# KC_Input_VAS_Schematic.net
KiCad netlist of a schematic drawn in Altium Designer
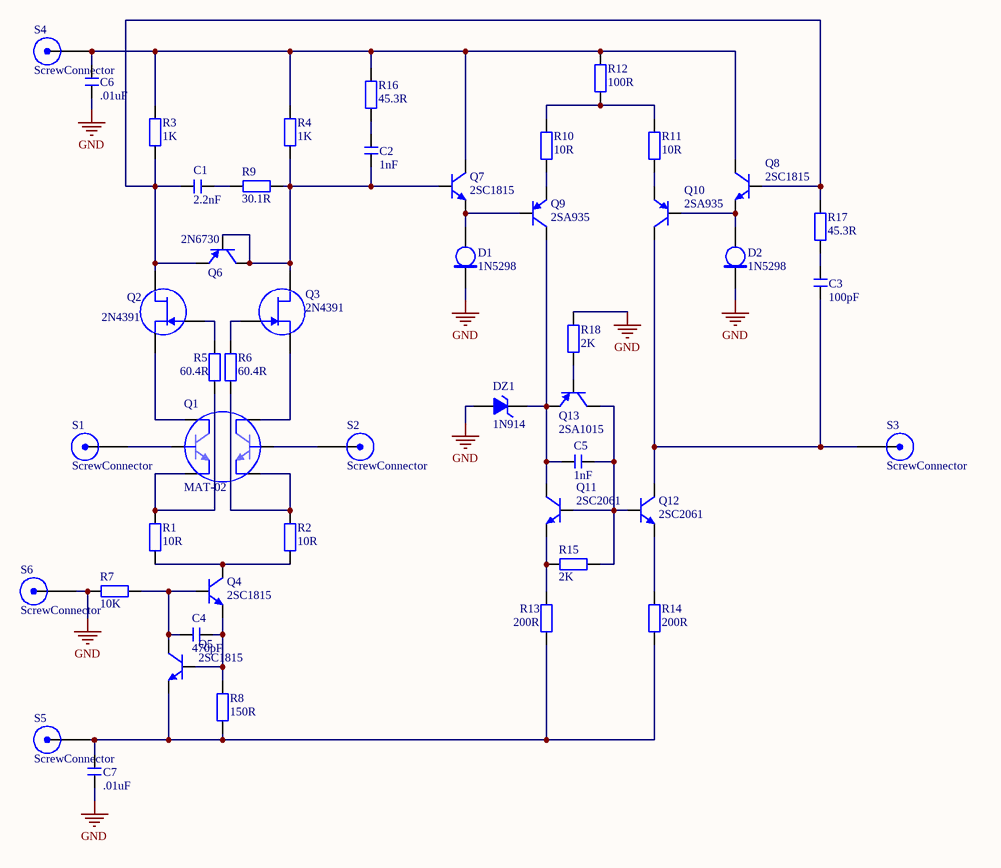
[diagram p0: KC_Input_VAS_Schematic.SchDoc]

(export (version "E")
  (design (tool "Eeschema 10.0.6"))
  (components
    (comp (ref "C1")
      (value "2.2nF")
      (footprint "CBB 6.3*6.3*5")
      (description "CBB电容")
      (fields (field (name "版权归属") "源创客"))
      (libsource (lib "电阻-电容-电感") (part "C-CBB"))
    )
    (comp (ref "C2")
      (value "1nF")
      (footprint "CBB 6.3*6.3*5")
      (description "CBB电容")
      (fields (field (name "版权归属") "源创客"))
      (libsource (lib "电阻-电容-电感") (part "C-CBB"))
    )
    (comp (ref "C3")
      (value "100pF")
      (footprint "CBB 6.3*6.3*5")
      (description "CBB电容")
      (fields (field (name "版权归属") "源创客"))
      (libsource (lib "电阻-电容-电感") (part "C-CBB"))
    )
    (comp (ref "C4")
      (value "470pF")
      (footprint "CBB 6.3*6.3*5")
      (description "CBB电容")
      (fields (field (name "版权归属") "源创客"))
      (libsource (lib "电阻-电容-电感") (part "C-CBB"))
    )
    (comp (ref "C5")
      (value "1nF")
      (footprint "CBB 6.3*6.3*5")
      (description "CBB电容")
      (fields (field (name "版权归属") "源创客"))
      (libsource (lib "电阻-电容-电感") (part "C-CBB"))
    )
    (comp (ref "C6")
      (value ".01uF")
      (footprint "CBB 6.3*6.3*5")
      (description "CBB电容")
      (fields (field (name "版权归属") "源创客"))
      (libsource (lib "电阻-电容-电感") (part "C-CBB"))
    )
    (comp (ref "C7")
      (value ".01uF")
      (footprint "CBB 6.3*6.3*5")
      (description "CBB电容")
      (fields (field (name "版权归属") "源创客"))
      (libsource (lib "电阻-电容-电感") (part "C-CBB"))
    )
    (comp (ref "D1")
      (value "1N5298")
      (footprint "DO-41V")
      (description "Current Regulator Diodes")
      (libsource (lib "二极管-整流桥") (part "1N5xxx"))
    )
    (comp (ref "D2")
      (value "1N5298")
      (footprint "DO-41V")
      (description "Current Regulator Diodes")
      (libsource (lib "二极管-整流桥") (part "1N5xxx"))
    )
    (comp (ref "DZ1")
      (value "1N914")
      (footprint "DO-41")
      (description "3V/0.5W稳压管")
      (fields (field (name "版权归属") "源创客"))
      (libsource (lib "二极管-整流桥") (part "1N4619"))
    )
    (comp (ref "Q1")
      (value "MAT-02")
      (footprint "DIP-8")
      (description "孪生对管-NPN型 40V/20ma")
      (libsource (lib "三极管") (part "MAT-02"))
    )
    (comp (ref "Q2")
      (value "2N4391")
      (footprint "TO-18_SMALLHOLE")
      (description "N沟道JFET开关管 40V/150ma")
      (libsource (lib "场效应管") (part "2N4391"))
    )
    (comp (ref "Q3")
      (value "2N4391")
      (footprint "TO-18_SMALLHOLE")
      (description "N沟道JFET开关管 40V/150ma")
      (libsource (lib "场效应管") (part "2N4391"))
    )
    (comp (ref "Q4")
      (value "2SC1815")
      (footprint "TO92A_SmallHole")
      (description "音频放大-NPN型")
      (libsource (lib "三极管") (part "2SC1815"))
    )
    (comp (ref "Q5")
      (value "2SC1815")
      (footprint "TO92A_SmallHole")
      (description "音频放大-NPN型")
      (libsource (lib "三极管") (part "2SC1815"))
    )
    (comp (ref "Q6")
      (value "2N6730")
      (footprint "TO92A_SmallHole")
      (description "中功率放大-PNP型")
      (libsource (lib "三极管") (part "2N6728/6729/6730"))
    )
    (comp (ref "Q7")
      (value "2SC1815")
      (footprint "TO92A_SmallHole")
      (description "音频放大-NPN型")
      (libsource (lib "三极管") (part "2SC1815"))
    )
    (comp (ref "Q8")
      (value "2SC1815")
      (footprint "TO92A_SmallHole")
      (description "音频放大-NPN型")
      (libsource (lib "三极管") (part "2SC1815"))
    )
    (comp (ref "Q9")
      (value "2SA935")
      (footprint "TO92A_SmallHole")
      (description "音频功放-PNP型 50V/500ma")
      (libsource (lib "三极管") (part "2SA935"))
    )
    (comp (ref "Q10")
      (value "2SA935")
      (footprint "TO92A_SmallHole")
      (description "音频功放-PNP型 50V/500ma")
      (libsource (lib "三极管") (part "2SA935"))
    )
    (comp (ref "Q11")
      (value "2SC2061")
      (footprint "TO92A_SmallHole")
      (description "音频放大-NPN型 50V/500ma")
      (libsource (lib "三极管") (part "2SC2061"))
    )
    (comp (ref "Q12")
      (value "2SC2061")
      (footprint "TO92A_SmallHole")
      (description "音频放大-NPN型 50V/500ma")
      (libsource (lib "三极管") (part "2SC2061"))
    )
    (comp (ref "Q13")
      (value "2SA1015")
      (footprint "TO92A_SmallHole")
      (description "音频放大-PNP型")
      (libsource (lib "三极管") (part "2SA1015"))
    )
    (comp (ref "R1")
      (value "10R")
      (footprint "RS 1/4W")
      (description "直插色环电阻")
      (fields (field (name "版权归属") "源创客"))
      (libsource (lib "电阻-电容-电感") (part "R-CRR"))
    )
    (comp (ref "R2")
      (value "10R")
      (footprint "RS 1/4W")
      (description "直插色环电阻")
      (fields (field (name "版权归属") "源创客"))
      (libsource (lib "电阻-电容-电感") (part "R-CRR"))
    )
    (comp (ref "R3")
      (value "1K")
      (footprint "RS 1/4W")
      (description "直插色环电阻")
      (fields (field (name "版权归属") "源创客"))
      (libsource (lib "电阻-电容-电感") (part "R-CRR"))
    )
    (comp (ref "R4")
      (value "1K")
      (footprint "RS 1/4W")
      (description "直插色环电阻")
      (fields (field (name "版权归属") "源创客"))
      (libsource (lib "电阻-电容-电感") (part "R-CRR"))
    )
    (comp (ref "R5")
      (value "60.4R")
      (footprint "RS 1/4W")
      (description "直插色环电阻")
      (fields (field (name "版权归属") "源创客"))
      (libsource (lib "电阻-电容-电感") (part "R-CRR"))
    )
    (comp (ref "R6")
      (value "60.4R")
      (footprint "RS 1/4W")
      (description "直插色环电阻")
      (fields (field (name "版权归属") "源创客"))
      (libsource (lib "电阻-电容-电感") (part "R-CRR"))
    )
    (comp (ref "R7")
      (value "10K")
      (footprint "RS 1/4W")
      (description "直插色环电阻")
      (fields (field (name "版权归属") "源创客"))
      (libsource (lib "电阻-电容-电感") (part "R-CRR"))
    )
    (comp (ref "R8")
      (value "150R")
      (footprint "RS 1/4W")
      (description "直插色环电阻")
      (fields (field (name "版权归属") "源创客"))
      (libsource (lib "电阻-电容-电感") (part "R-CRR"))
    )
    (comp (ref "R9")
      (value "30.1R")
      (footprint "RS 1/4W")
      (description "直插色环电阻")
      (fields (field (name "版权归属") "源创客"))
      (libsource (lib "电阻-电容-电感") (part "R-CRR"))
    )
    (comp (ref "R10")
      (value "10R")
      (footprint "RS 1/4W")
      (description "直插色环电阻")
      (fields (field (name "版权归属") "源创客"))
      (libsource (lib "电阻-电容-电感") (part "R-CRR"))
    )
    (comp (ref "R11")
      (value "10R")
      (footprint "RS 1/4W")
      (description "直插色环电阻")
      (fields (field (name "版权归属") "源创客"))
      (libsource (lib "电阻-电容-电感") (part "R-CRR"))
    )
    (comp (ref "R12")
      (value "100R")
      (footprint "RS 1/4W")
      (description "直插色环电阻")
      (fields (field (name "版权归属") "源创客"))
      (libsource (lib "电阻-电容-电感") (part "R-CRR"))
    )
    (comp (ref "R13")
      (value "200R")
      (footprint "RS 1/4W")
      (description "直插色环电阻")
      (fields (field (name "版权归属") "源创客"))
      (libsource (lib "电阻-电容-电感") (part "R-CRR"))
    )
    (comp (ref "R14")
      (value "200R")
      (footprint "RS 1/4W")
      (description "直插色环电阻")
      (fields (field (name "版权归属") "源创客"))
      (libsource (lib "电阻-电容-电感") (part "R-CRR"))
    )
    (comp (ref "R15")
      (value "2K")
      (footprint "RS 1/4W")
      (description "直插色环电阻")
      (fields (field (name "版权归属") "源创客"))
      (libsource (lib "电阻-电容-电感") (part "R-CRR"))
    )
    (comp (ref "R16")
      (value "45.3R")
      (footprint "RS 1/4W")
      (description "直插色环电阻")
      (fields (field (name "版权归属") "源创客"))
      (libsource (lib "电阻-电容-电感") (part "R-CRR"))
    )
    (comp (ref "R17")
      (value "45.3R")
      (footprint "RS 1/4W")
      (description "直插色环电阻")
      (fields (field (name "版权归属") "源创客"))
      (libsource (lib "电阻-电容-电感") (part "R-CRR"))
    )
    (comp (ref "R18")
      (value "2K")
      (footprint "RS 1/4W")
      (description "直插色环电阻")
      (fields (field (name "版权归属") "源创客"))
      (libsource (lib "电阻-电容-电感") (part "R-CRR"))
    )
    (comp (ref "S1")
      (value "ScrewConnector")
      (footprint "Screw-M2-s")
      (description "Screw Connector")
      (libsource (lib "Connectors") (part "ScrewConnector"))
    )
    (comp (ref "S2")
      (value "ScrewConnector")
      (footprint "Screw-M2-s")
      (description "Screw Connector")
      (libsource (lib "Connectors") (part "ScrewConnector"))
    )
    (comp (ref "S3")
      (value "ScrewConnector")
      (footprint "Screw-M2-s")
      (description "Screw Connector")
      (libsource (lib "Connectors") (part "ScrewConnector"))
    )
    (comp (ref "S4")
      (value "ScrewConnector")
      (footprint "Screw-M2-s")
      (description "Screw Connector")
      (libsource (lib "Connectors") (part "ScrewConnector"))
    )
    (comp (ref "S5")
      (value "ScrewConnector")
      (footprint "Screw-M2-s")
      (description "Screw Connector")
      (libsource (lib "Connectors") (part "ScrewConnector"))
    )
    (comp (ref "S6")
      (value "ScrewConnector")
      (footprint "Screw-M2-s")
      (description "Screw Connector")
      (libsource (lib "Connectors") (part "ScrewConnector"))
    )
  )
  (nets
    (net (code "1") (name "GND") (class "Default")
      (node (ref "C6") (pin "2") (pinfunction "2_2") (pintype "passive"))
      (node (ref "C7") (pin "1") (pinfunction "1_1") (pintype "passive"))
      (node (ref "D1") (pin "1") (pinfunction "Cathode_1") (pintype "passive"))
      (node (ref "D2") (pin "1") (pinfunction "Cathode_1") (pintype "passive"))
      (node (ref "DZ1") (pin "1") (pinfunction "A_1") (pintype "passive"))
      (node (ref "R18") (pin "2") (pinfunction "2_2") (pintype "passive"))
      (node (ref "R7") (pin "1") (pinfunction "1_1") (pintype "passive"))
      (node (ref "S6") (pin "1") (pinfunction "X_1") (pintype "passive"))
    )
    (net (code "2") (name "Net-(C1-Pad2)") (class "Default")
      (node (ref "C1") (pin "2") (pinfunction "2_2") (pintype "passive"))
      (node (ref "R9") (pin "1") (pinfunction "1_1") (pintype "passive"))
    )
    (net (code "3") (name "Net-(C2-Pad1)") (class "Default")
      (node (ref "C2") (pin "1") (pinfunction "1_1") (pintype "passive"))
      (node (ref "R16") (pin "1") (pinfunction "1_1") (pintype "passive"))
    )
    (net (code "4") (name "Net-(C3-Pad2)") (class "Default")
      (node (ref "C3") (pin "2") (pinfunction "2_2") (pintype "passive"))
      (node (ref "R17") (pin "1") (pinfunction "1_1") (pintype "passive"))
    )
    (net (code "5") (name "Net-(D1-Anode)") (class "Default")
      (node (ref "D1") (pin "2") (pinfunction "Anode_2") (pintype "passive"))
      (node (ref "Q7") (pin "1") (pinfunction "E_1") (pintype "passive"))
      (node (ref "Q9") (pin "3") (pinfunction "B_3") (pintype "passive"))
    )
    (net (code "6") (name "Net-(D2-Anode)") (class "Default")
      (node (ref "D2") (pin "2") (pinfunction "Anode_2") (pintype "passive"))
      (node (ref "Q10") (pin "3") (pinfunction "B_3") (pintype "passive"))
      (node (ref "Q8") (pin "1") (pinfunction "E_1") (pintype "passive"))
    )
    (net (code "7") (name "Net-(DZ1-K)") (class "Default")
      (node (ref "C5") (pin "1") (pinfunction "1_1") (pintype "passive"))
      (node (ref "DZ1") (pin "2") (pinfunction "K_2") (pintype "passive"))
      (node (ref "Q11") (pin "2") (pinfunction "C_2") (pintype "passive"))
      (node (ref "Q13") (pin "1") (pinfunction "E_1") (pintype "passive"))
      (node (ref "Q9") (pin "2") (pinfunction "C_2") (pintype "passive"))
    )
    (net (code "8") (name "Net-(Q1-E-Pad3)") (class "Default")
      (node (ref "Q1") (pin "3") (pinfunction "E_3") (pintype "passive"))
      (node (ref "R1") (pin "2") (pinfunction "2_2") (pintype "passive"))
      (node (ref "R5") (pin "1") (pinfunction "1_1") (pintype "passive"))
    )
    (net (code "9") (name "Net-(Q1-E-Pad5)") (class "Default")
      (node (ref "Q1") (pin "5") (pinfunction "E_5") (pintype "passive"))
      (node (ref "R2") (pin "2") (pinfunction "2_2") (pintype "passive"))
      (node (ref "R6") (pin "1") (pinfunction "1_1") (pintype "passive"))
    )
    (net (code "10") (name "Net-(Q2-D)") (class "Default")
      (node (ref "C1") (pin "1") (pinfunction "1_1") (pintype "passive"))
      (node (ref "Q2") (pin "3") (pinfunction "D_3") (pintype "passive"))
      (node (ref "Q6") (pin "1") (pinfunction "E_1") (pintype "passive"))
      (node (ref "Q8") (pin "3") (pinfunction "B_3") (pintype "passive"))
      (node (ref "R17") (pin "2") (pinfunction "2_2") (pintype "passive"))
      (node (ref "R3") (pin "1") (pinfunction "1_1") (pintype "passive"))
    )
    (net (code "11") (name "Net-(Q2-G)") (class "Default")
      (node (ref "Q2") (pin "2") (pinfunction "G_2") (pintype "passive"))
      (node (ref "R5") (pin "2") (pinfunction "2_2") (pintype "passive"))
    )
    (net (code "12") (name "Net-(Q2-S)") (class "Default")
      (node (ref "Q1") (pin "1") (pinfunction "C_1") (pintype "passive"))
      (node (ref "Q2") (pin "1") (pinfunction "S_1") (pintype "passive"))
    )
    (net (code "13") (name "Net-(Q3-D)") (class "Default")
      (node (ref "C2") (pin "2") (pinfunction "2_2") (pintype "passive"))
      (node (ref "Q3") (pin "3") (pinfunction "D_3") (pintype "passive"))
      (node (ref "Q6") (pin "2") (pinfunction "C_2") (pintype "passive"))
      (node (ref "Q6") (pin "3") (pinfunction "B_3") (pintype "passive"))
      (node (ref "Q7") (pin "3") (pinfunction "B_3") (pintype "passive"))
      (node (ref "R4") (pin "1") (pinfunction "1_1") (pintype "passive"))
      (node (ref "R9") (pin "2") (pinfunction "2_2") (pintype "passive"))
    )
    (net (code "14") (name "Net-(Q3-G)") (class "Default")
      (node (ref "Q3") (pin "2") (pinfunction "G_2") (pintype "passive"))
      (node (ref "R6") (pin "2") (pinfunction "2_2") (pintype "passive"))
    )
    (net (code "15") (name "Net-(Q3-S)") (class "Default")
      (node (ref "Q1") (pin "7") (pinfunction "C_7") (pintype "passive"))
      (node (ref "Q3") (pin "1") (pinfunction "S_1") (pintype "passive"))
    )
    (net (code "16") (name "Net-(Q4-B)") (class "Default")
      (node (ref "C4") (pin "1") (pinfunction "1_1") (pintype "passive"))
      (node (ref "Q4") (pin "3") (pinfunction "B_3") (pintype "passive"))
      (node (ref "Q5") (pin "2") (pinfunction "C_2") (pintype "passive"))
      (node (ref "R7") (pin "2") (pinfunction "2_2") (pintype "passive"))
    )
    (net (code "17") (name "Net-(Q4-C)") (class "Default")
      (node (ref "Q4") (pin "2") (pinfunction "C_2") (pintype "passive"))
      (node (ref "R1") (pin "1") (pinfunction "1_1") (pintype "passive"))
      (node (ref "R2") (pin "1") (pinfunction "1_1") (pintype "passive"))
    )
    (net (code "18") (name "Net-(Q4-E)") (class "Default")
      (node (ref "C4") (pin "2") (pinfunction "2_2") (pintype "passive"))
      (node (ref "Q4") (pin "1") (pinfunction "E_1") (pintype "passive"))
      (node (ref "Q5") (pin "3") (pinfunction "B_3") (pintype "passive"))
      (node (ref "R8") (pin "1") (pinfunction "1_1") (pintype "passive"))
    )
    (net (code "19") (name "Net-(Q5-E)") (class "Default")
      (node (ref "C7") (pin "2") (pinfunction "2_2") (pintype "passive"))
      (node (ref "Q5") (pin "1") (pinfunction "E_1") (pintype "passive"))
      (node (ref "R13") (pin "1") (pinfunction "1_1") (pintype "passive"))
      (node (ref "R14") (pin "1") (pinfunction "1_1") (pintype "passive"))
      (node (ref "R8") (pin "2") (pinfunction "2_2") (pintype "passive"))
      (node (ref "S5") (pin "1") (pinfunction "X_1") (pintype "passive"))
    )
    (net (code "20") (name "Net-(Q7-C)") (class "Default")
      (node (ref "C6") (pin "1") (pinfunction "1_1") (pintype "passive"))
      (node (ref "Q7") (pin "2") (pinfunction "C_2") (pintype "passive"))
      (node (ref "Q8") (pin "2") (pinfunction "C_2") (pintype "passive"))
      (node (ref "R12") (pin "2") (pinfunction "2_2") (pintype "passive"))
      (node (ref "R16") (pin "2") (pinfunction "2_2") (pintype "passive"))
      (node (ref "R3") (pin "2") (pinfunction "2_2") (pintype "passive"))
      (node (ref "R4") (pin "2") (pinfunction "2_2") (pintype "passive"))
      (node (ref "S4") (pin "1") (pinfunction "X_1") (pintype "passive"))
    )
    (net (code "21") (name "Net-(Q9-E)") (class "Default")
      (node (ref "Q9") (pin "1") (pinfunction "E_1") (pintype "passive"))
      (node (ref "R10") (pin "1") (pinfunction "1_1") (pintype "passive"))
    )
    (net (code "22") (name "Net-(Q10-C)") (class "Default")
      (node (ref "C3") (pin "1") (pinfunction "1_1") (pintype "passive"))
      (node (ref "Q10") (pin "2") (pinfunction "C_2") (pintype "passive"))
      (node (ref "Q12") (pin "2") (pinfunction "C_2") (pintype "passive"))
      (node (ref "S3") (pin "1") (pinfunction "X_1") (pintype "passive"))
    )
    (net (code "23") (name "Net-(Q10-E)") (class "Default")
      (node (ref "Q10") (pin "1") (pinfunction "E_1") (pintype "passive"))
      (node (ref "R11") (pin "1") (pinfunction "1_1") (pintype "passive"))
    )
    (net (code "24") (name "Net-(Q11-B)") (class "Default")
      (node (ref "C5") (pin "2") (pinfunction "2_2") (pintype "passive"))
      (node (ref "Q11") (pin "3") (pinfunction "B_3") (pintype "passive"))
      (node (ref "Q12") (pin "3") (pinfunction "B_3") (pintype "passive"))
      (node (ref "Q13") (pin "2") (pinfunction "C_2") (pintype "passive"))
      (node (ref "R15") (pin "1") (pinfunction "1_1") (pintype "passive"))
    )
    (net (code "25") (name "Net-(Q11-E)") (class "Default")
      (node (ref "Q11") (pin "1") (pinfunction "E_1") (pintype "passive"))
      (node (ref "R13") (pin "2") (pinfunction "2_2") (pintype "passive"))
      (node (ref "R15") (pin "2") (pinfunction "2_2") (pintype "passive"))
    )
    (net (code "26") (name "Net-(Q12-E)") (class "Default")
      (node (ref "Q12") (pin "1") (pinfunction "E_1") (pintype "passive"))
      (node (ref "R14") (pin "2") (pinfunction "2_2") (pintype "passive"))
    )
    (net (code "27") (name "Net-(Q13-B)") (class "Default")
      (node (ref "Q13") (pin "3") (pinfunction "B_3") (pintype "passive"))
      (node (ref "R18") (pin "1") (pinfunction "1_1") (pintype "passive"))
    )
    (net (code "28") (name "Net-(R10-Pad2)") (class "Default")
      (node (ref "R10") (pin "2") (pinfunction "2_2") (pintype "passive"))
      (node (ref "R11") (pin "2") (pinfunction "2_2") (pintype "passive"))
      (node (ref "R12") (pin "1") (pinfunction "1_1") (pintype "passive"))
    )
    (net (code "29") (name "Net-(S1-X)") (class "Default")
      (node (ref "Q1") (pin "2") (pinfunction "B_2") (pintype "passive"))
      (node (ref "S1") (pin "1") (pinfunction "X_1") (pintype "passive"))
    )
    (net (code "30") (name "Net-(S2-X)") (class "Default")
      (node (ref "Q1") (pin "6") (pinfunction "B_6") (pintype "passive"))
      (node (ref "S2") (pin "1") (pinfunction "X_1") (pintype "passive"))
    )
  )
)
